# 01_V5_SYS.net
KiCad netlist of a schematic drawn in Altium Designer
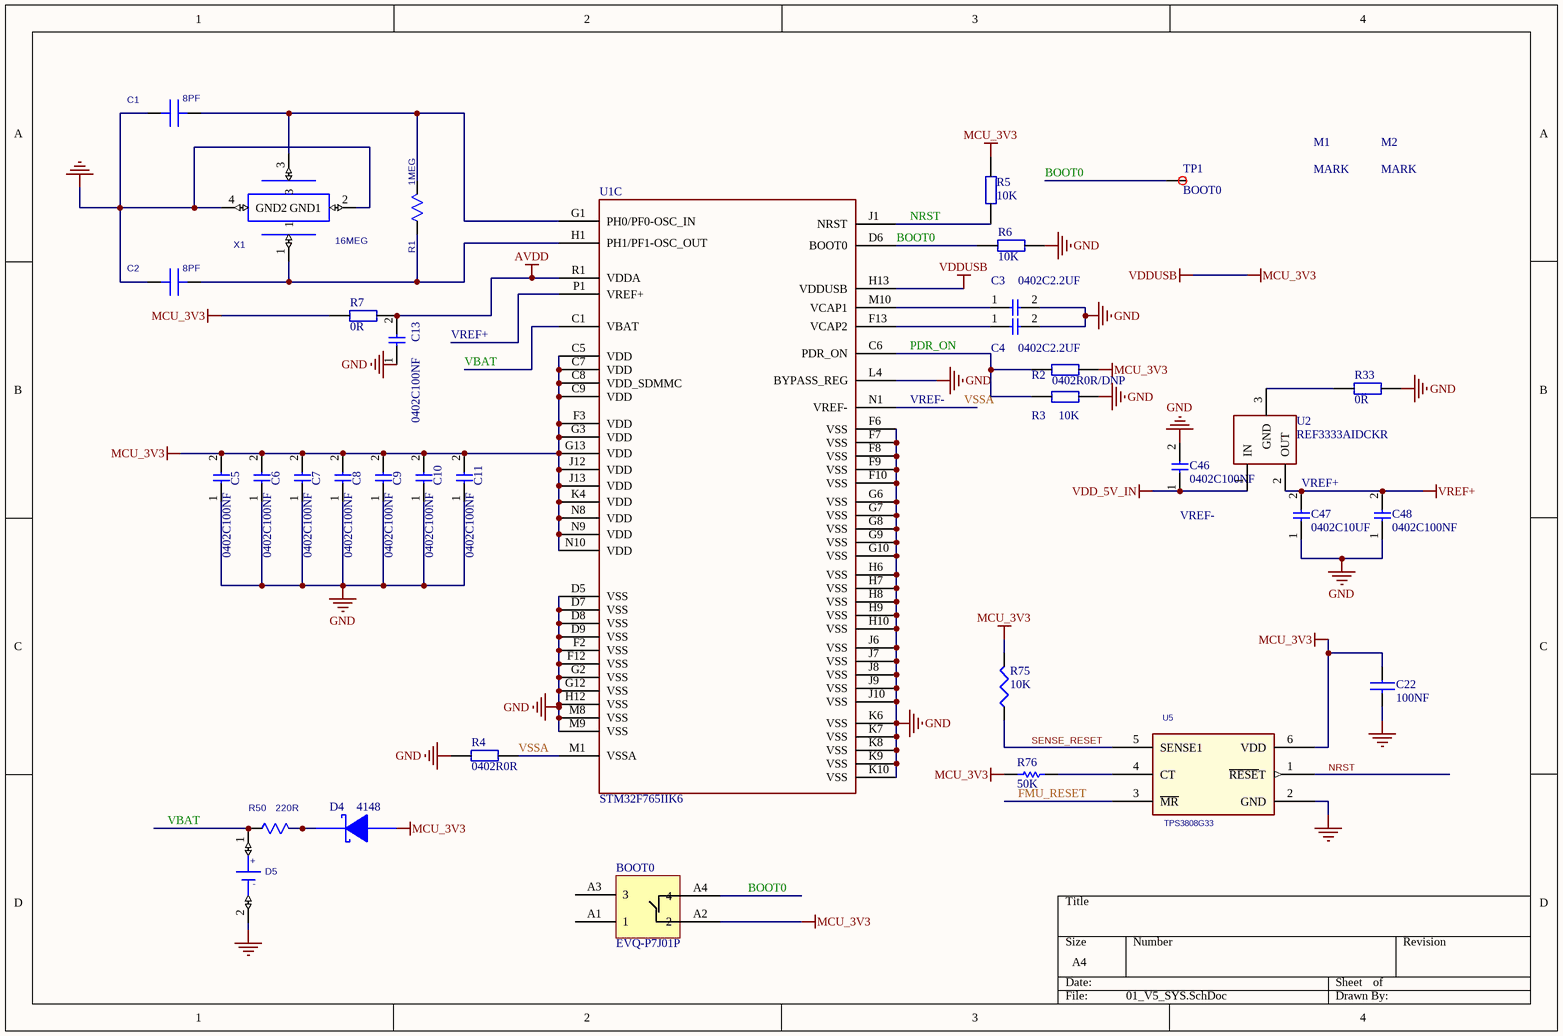
[diagram p0: 01_V5_SYS.SchDoc]

(export (version "E")
  (design (tool "Eeschema 10.0.6"))
  (components
    (comp (ref "BOOT0")
      (value "EVQ-P7J01P")
      (footprint "EVQ-P7J01P")
      (libsource (lib "hack") (part "EVQ-P7J01P"))
    )
    (comp (ref "C1") (value "8PF") (footprint "SC0402") (libsource (lib "*") (part "C")))
    (comp (ref "C2") (value "8PF") (footprint "SC0402") (libsource (lib "*") (part "C")))
    (comp (ref "C3") (value "0402C2.2UF") (footprint "0402C") (libsource (lib "CUAV") (part "0402C2.2UF")))
    (comp (ref "C4") (value "0402C2.2UF") (footprint "0402C") (libsource (lib "CUAV") (part "0402C2.2UF")))
    (comp (ref "C5")
      (value "0402C100NF")
      (footprint "0402C")
      (description "50V 5%")
      (libsource (lib "CUAV") (part "0402C100NF"))
    )
    (comp (ref "C6")
      (value "0402C100NF")
      (footprint "0402C")
      (description "50V 5%")
      (libsource (lib "CUAV") (part "0402C100NF"))
    )
    (comp (ref "C7")
      (value "0402C100NF")
      (footprint "0402C")
      (description "50V 5%")
      (libsource (lib "CUAV") (part "0402C100NF"))
    )
    (comp (ref "C8")
      (value "0402C100NF")
      (footprint "0402C")
      (description "50V 5%")
      (libsource (lib "CUAV") (part "0402C100NF"))
    )
    (comp (ref "C9")
      (value "0402C100NF")
      (footprint "0402C")
      (description "50V 5%")
      (libsource (lib "CUAV") (part "0402C100NF"))
    )
    (comp (ref "C10")
      (value "0402C100NF")
      (footprint "0402C")
      (description "50V 5%")
      (libsource (lib "CUAV") (part "0402C100NF"))
    )
    (comp (ref "C11")
      (value "0402C100NF")
      (footprint "0402C")
      (description "50V 5%")
      (libsource (lib "CUAV") (part "0402C100NF"))
    )
    (comp (ref "C13")
      (value "0402C100NF")
      (footprint "0402C")
      (description "50V 5%")
      (libsource (lib "CUAV") (part "0402C100NF"))
    )
    (comp (ref "C22")
      (value "100NF")
      (footprint "0402cap")
      (libsource (lib "Integrated_Library_RF_FEB_2012") (part "C1005X5R1H104K"))
    )
    (comp (ref "C46") (value "0402C100NF") (footprint "0402C") (libsource (lib "CUAV") (part "0402C2.2UF")))
    (comp (ref "C47") (value "0402C10UF") (footprint "0402C") (libsource (lib "CUAV") (part "0402C2.2UF")))
    (comp (ref "C48") (value "0402C100NF") (footprint "0402C") (libsource (lib "CUAV") (part "0402C2.2UF")))
    (comp (ref "D4")
      (value "4148")
      (footprint "SOD323")
      (description "STPS20M100SG-TR")
      (libsource (lib "TI WEBENCH") (part "D1"))
    )
    (comp (ref "D5")
      (value "PAS414HR-VE5R")
      (footprint "PAS414R-S-VE5R")
      (libsource (lib "*") (part "PWR1-2_1"))
    )
    (comp (ref "M1") (value "MARK") (footprint "MARK") (libsource (lib "CUAV") (part "MARK")))
    (comp (ref "M2") (value "MARK") (footprint "MARK") (libsource (lib "CUAV") (part "MARK")))
    (comp (ref "R1") (value "1MEG") (footprint "SR0402") (libsource (lib "*") (part "R")))
    (comp (ref "R2")
      (value "0402R0R/DNP")
      (footprint "0402R")
      (description "0402R0R 1%")
      (libsource (lib "") (part "0402R0R_2"))
    )
    (comp (ref "R3")
      (value "10K")
      (footprint "0402R")
      (description "0402R0R 1%")
      (libsource (lib "") (part "0402R0R_2"))
    )
    (comp (ref "R4")
      (value "0402R0R")
      (footprint "0402R")
      (description "0402R0R 1%")
      (libsource (lib "") (part "0402R0R_2"))
    )
    (comp (ref "R5")
      (value "10K")
      (footprint "0402R")
      (description "0402R0R 1%")
      (libsource (lib "") (part "0402R0R_1"))
    )
    (comp (ref "R6")
      (value "10K")
      (footprint "0402R")
      (description "0402R0R 1%")
      (libsource (lib "CUAV") (part "0402R0R"))
    )
    (comp (ref "R7")
      (value "0R")
      (footprint "0402R")
      (description "0402R0R 1%")
      (libsource (lib "CUAV") (part "0402R0R"))
    )
    (comp (ref "R33")
      (value "0R")
      (footprint "0402R")
      (description "0402R0R 1%")
      (libsource (lib "CUAV") (part "0402R0R"))
    )
    (comp (ref "R50") (value "220R") (footprint "0402r") (libsource (lib "*") (part "R")))
    (comp (ref "R75")
      (value "10K")
      (footprint "R0402")
      (libsource (lib "Integrated_Library_RF_FEB_2012") (part "RMCF0402FT4K99"))
    )
    (comp (ref "R76")
      (value "50K")
      (footprint "0402R")
      (description "Semiconductor Resistor")
      (libsource (lib "Miscellaneous Devices") (part "Res Semi"))
    )
    (comp (ref "TP1")
      (value "BOOT0")
      (footprint "TP0.75")
      (description "TP_0.75MM")
      (libsource (lib "CUAV") (part "TP_0.75"))
    )
    (comp (ref "U1")
      (value "STM32F765IIK6")
      (footprint "UFBGA176")
      (libsource (lib "CUAV") (part "STM32F765IIK6"))
    )
    (comp (ref "U2")
      (value "REF3333AIDCKR")
      (footprint "SC70")
      (libsource (lib "CUAV") (part "REF3333AIDCKT"))
    )
    (comp (ref "U5")
      (value "TPS3808G33")
      (footprint "SOT-23-6")
      (description "IC VOLT SUPERVISOR 0.9V SOT23-6")
      (fields (field (name "PART #") "102020-0009R") (field (name "MANUFACTURER") "Texas Instruments"))
      (libsource (lib "Integrated_Library_RF_FEB_2012") (part "TPS3808G09DBVR"))
    )
    (comp (ref "X1") (value "16MEG") (footprint "3225") (libsource (lib "*") (part "X_B")))
  )
  (nets
    (net (code "1") (name "/BOOT0") (class "Default")
      (node (ref "BOOT0") (pin "A4") (pinfunction "4_A4") (pintype "passive"))
      (node (ref "R6") (pin "2") (pintype "passive"))
      (node (ref "TP1") (pin "0") (pintype "passive"))
      (node (ref "U1") (pin "D6") (pinfunction "BOOT0_D6") (pintype "passive"))
    )
    (net (code "2") (name "/FMU_RESET") (class "Default")
      (node (ref "U5") (pin "3") (pinfunction "~{MR}_3") (pintype "passive"))
    )
    (net (code "3") (name "/NRST") (class "Default")
      (node (ref "R5") (pin "1") (pintype "passive"))
      (node (ref "U1") (pin "J1") (pinfunction "NRST_J1") (pintype "passive"))
      (node (ref "U5") (pin "1") (pinfunction "~{RESE}T_1") (pintype "output"))
    )
    (net (code "4") (name "/PDR_ON") (class "Default")
      (node (ref "R2") (pin "1") (pintype "passive"))
      (node (ref "R3") (pin "1") (pintype "passive"))
      (node (ref "U1") (pin "C6") (pinfunction "PDR_ON_C6") (pintype "passive"))
    )
    (net (code "5") (name "/SENSE_RESET") (class "Default")
      (node (ref "R75") (pin "1") (pinfunction "1_1") (pintype "passive"))
      (node (ref "U5") (pin "5") (pinfunction "SENSE1_5") (pintype "passive"))
    )
    (net (code "6") (name "/VBAT") (class "Default")
      (node (ref "D5") (pin "1") (pinfunction "+_1") (pintype "bidirectional"))
      (node (ref "R50") (pin "1") (pinfunction "A_1") (pintype "bidirectional"))
      (node (ref "U1") (pin "C1") (pinfunction "VBAT_C1") (pintype "passive"))
    )
    (net (code "7") (name "/VREF-") (class "Default")
      (node (ref "R4") (pin "2") (pintype "passive"))
      (node (ref "U1") (pin "M1") (pinfunction "VSSA_M1") (pintype "passive"))
      (node (ref "U1") (pin "N1") (pinfunction "VREF-_N1") (pintype "passive"))
    )
    (net (code "8") (name "AVDD") (class "Default")
      (node (ref "C13") (pin "2") (pintype "passive"))
      (node (ref "R7") (pin "1") (pintype "passive"))
      (node (ref "U1") (pin "R1") (pinfunction "VDDA_R1") (pintype "passive"))
    )
    (net (code "9") (name "GND") (class "Default")
      (node (ref "C1") (pin "1") (pinfunction "A_1") (pintype "bidirectional"))
      (node (ref "C10") (pin "1") (pintype "passive"))
      (node (ref "C11") (pin "1") (pintype "passive"))
      (node (ref "C13") (pin "1") (pintype "passive"))
      (node (ref "C2") (pin "1") (pinfunction "A_1") (pintype "bidirectional"))
      (node (ref "C22") (pin "2") (pinfunction "2_2") (pintype "passive"))
      (node (ref "C3") (pin "2") (pintype "passive"))
      (node (ref "C4") (pin "2") (pintype "passive"))
      (node (ref "C46") (pin "2") (pintype "passive"))
      (node (ref "C47") (pin "1") (pintype "passive"))
      (node (ref "C48") (pin "1") (pintype "passive"))
      (node (ref "C5") (pin "1") (pintype "passive"))
      (node (ref "C6") (pin "1") (pintype "passive"))
      (node (ref "C7") (pin "1") (pintype "passive"))
      (node (ref "C8") (pin "1") (pintype "passive"))
      (node (ref "C9") (pin "1") (pintype "passive"))
      (node (ref "D5") (pin "2") (pinfunction "-_2") (pintype "bidirectional"))
      (node (ref "R3") (pin "2") (pintype "passive"))
      (node (ref "R33") (pin "1") (pintype "passive"))
      (node (ref "R4") (pin "1") (pintype "passive"))
      (node (ref "R6") (pin "1") (pintype "passive"))
      (node (ref "U1") (pin "D5") (pinfunction "VSS_D5") (pintype "passive"))
      (node (ref "U1") (pin "D7") (pinfunction "VSS_D7") (pintype "passive"))
      (node (ref "U1") (pin "D8") (pinfunction "VSS_D8") (pintype "passive"))
      (node (ref "U1") (pin "D9") (pinfunction "VSS_D9") (pintype "passive"))
      (node (ref "U1") (pin "F10") (pinfunction "VSS_F10") (pintype "passive"))
      (node (ref "U1") (pin "F12") (pinfunction "VSS_F12") (pintype "passive"))
      (node (ref "U1") (pin "F2") (pinfunction "VSS_F2") (pintype "passive"))
      (node (ref "U1") (pin "F6") (pinfunction "VSS_F6") (pintype "passive"))
      (node (ref "U1") (pin "F7") (pinfunction "VSS_F7") (pintype "passive"))
      (node (ref "U1") (pin "F8") (pinfunction "VSS_F8") (pintype "passive"))
      (node (ref "U1") (pin "F9") (pinfunction "VSS_F9") (pintype "passive"))
      (node (ref "U1") (pin "G10") (pinfunction "VSS_G10") (pintype "passive"))
      (node (ref "U1") (pin "G12") (pinfunction "VSS_G12") (pintype "passive"))
      (node (ref "U1") (pin "G2") (pinfunction "VSS_G2") (pintype "passive"))
      (node (ref "U1") (pin "G6") (pinfunction "VSS_G6") (pintype "passive"))
      (node (ref "U1") (pin "G7") (pinfunction "VSS_G7") (pintype "passive"))
      (node (ref "U1") (pin "G8") (pinfunction "VSS_G8") (pintype "passive"))
      (node (ref "U1") (pin "G9") (pinfunction "VSS_G9") (pintype "passive"))
      (node (ref "U1") (pin "H10") (pinfunction "VSS_H10") (pintype "passive"))
      (node (ref "U1") (pin "H12") (pinfunction "VSS_H12") (pintype "passive"))
      (node (ref "U1") (pin "H6") (pinfunction "VSS_H6") (pintype "passive"))
      (node (ref "U1") (pin "H7") (pinfunction "VSS_H7") (pintype "passive"))
      (node (ref "U1") (pin "H8") (pinfunction "VSS_H8") (pintype "passive"))
      (node (ref "U1") (pin "H9") (pinfunction "VSS_H9") (pintype "passive"))
      (node (ref "U1") (pin "J10") (pinfunction "VSS_J10") (pintype "passive"))
      (node (ref "U1") (pin "J6") (pinfunction "VSS_J6") (pintype "passive"))
      (node (ref "U1") (pin "J7") (pinfunction "VSS_J7") (pintype "passive"))
      (node (ref "U1") (pin "J8") (pinfunction "VSS_J8") (pintype "passive"))
      (node (ref "U1") (pin "J9") (pinfunction "VSS_J9") (pintype "passive"))
      (node (ref "U1") (pin "K10") (pinfunction "VSS_K10") (pintype "passive"))
      (node (ref "U1") (pin "K6") (pinfunction "VSS_K6") (pintype "passive"))
      (node (ref "U1") (pin "K7") (pinfunction "VSS_K7") (pintype "passive"))
      (node (ref "U1") (pin "K8") (pinfunction "VSS_K8") (pintype "passive"))
      (node (ref "U1") (pin "K9") (pinfunction "VSS_K9") (pintype "passive"))
      (node (ref "U1") (pin "L4") (pinfunction "BYPASS_REG_L4") (pintype "passive"))
      (node (ref "U1") (pin "M8") (pinfunction "VSS_M8") (pintype "passive"))
      (node (ref "U1") (pin "M9") (pinfunction "VSS_M9") (pintype "passive"))
      (node (ref "U5") (pin "2") (pinfunction "GND_2") (pintype "passive"))
      (node (ref "X1") (pin "2") (pinfunction "GND1_2") (pintype "bidirectional"))
      (node (ref "X1") (pin "4") (pinfunction "GND2_4") (pintype "bidirectional"))
    )
    (net (code "10") (name "MCU_3V3") (class "Default")
      (node (ref "BOOT0") (pin "A2") (pinfunction "2_A2") (pintype "passive"))
      (node (ref "C10") (pin "2") (pintype "passive"))
      (node (ref "C11") (pin "2") (pintype "passive"))
      (node (ref "C22") (pin "1") (pinfunction "1_1") (pintype "passive"))
      (node (ref "C5") (pin "2") (pintype "passive"))
      (node (ref "C6") (pin "2") (pintype "passive"))
      (node (ref "C7") (pin "2") (pintype "passive"))
      (node (ref "C8") (pin "2") (pintype "passive"))
      (node (ref "C9") (pin "2") (pintype "passive"))
      (node (ref "D4") (pin "A") (pinfunction "A_A") (pintype "passive"))
      (node (ref "R2") (pin "2") (pintype "passive"))
      (node (ref "R5") (pin "2") (pintype "passive"))
      (node (ref "R7") (pin "2") (pintype "passive"))
      (node (ref "R75") (pin "2") (pinfunction "2_2") (pintype "passive"))
      (node (ref "R76") (pin "2") (pinfunction "2_2") (pintype "passive"))
      (node (ref "U1") (pin "C5") (pinfunction "VDD_C5") (pintype "passive"))
      (node (ref "U1") (pin "C7") (pinfunction "VDD_C7") (pintype "passive"))
      (node (ref "U1") (pin "C8") (pinfunction "VDD_SDMMC_C8") (pintype "passive"))
      (node (ref "U1") (pin "C9") (pinfunction "VDD_C9") (pintype "passive"))
      (node (ref "U1") (pin "F3") (pinfunction "VDD_F3") (pintype "passive"))
      (node (ref "U1") (pin "G13") (pinfunction "VDD_G13") (pintype "passive"))
      (node (ref "U1") (pin "G3") (pinfunction "VDD_G3") (pintype "passive"))
      (node (ref "U1") (pin "H13") (pinfunction "VDDUSB_H13") (pintype "passive"))
      (node (ref "U1") (pin "J12") (pinfunction "VDD_J12") (pintype "passive"))
      (node (ref "U1") (pin "J13") (pinfunction "VDD_J13") (pintype "passive"))
      (node (ref "U1") (pin "K4") (pinfunction "VDD_K4") (pintype "passive"))
      (node (ref "U1") (pin "N10") (pinfunction "VDD_N10") (pintype "passive"))
      (node (ref "U1") (pin "N8") (pinfunction "VDD_N8") (pintype "passive"))
      (node (ref "U1") (pin "N9") (pinfunction "VDD_N9") (pintype "passive"))
      (node (ref "U5") (pin "6") (pinfunction "VDD_6") (pintype "passive"))
    )
    (net (code "11") (name "Net-(C1-B)") (class "Default")
      (node (ref "C1") (pin "2") (pinfunction "B_2") (pintype "bidirectional"))
      (node (ref "R1") (pin "2") (pinfunction "B_2") (pintype "bidirectional"))
      (node (ref "U1") (pin "G1") (pinfunction "PH0/PF0-OSC_IN_G1") (pintype "passive"))
      (node (ref "X1") (pin "3") (pinfunction "3_3") (pintype "bidirectional"))
    )
    (net (code "12") (name "Net-(C2-B)") (class "Default")
      (node (ref "C2") (pin "2") (pinfunction "B_2") (pintype "bidirectional"))
      (node (ref "R1") (pin "1") (pinfunction "A_1") (pintype "bidirectional"))
      (node (ref "U1") (pin "H1") (pinfunction "PH1/PF1-OSC_OUT_H1") (pintype "passive"))
      (node (ref "X1") (pin "1") (pinfunction "1_1") (pintype "bidirectional"))
    )
    (net (code "13") (name "Net-(R50-B)") (class "Default")
      (node (ref "D4") (pin "K") (pinfunction "K_K") (pintype "passive"))
      (node (ref "R50") (pin "2") (pinfunction "B_2") (pintype "bidirectional"))
    )
    (net (code "14") (name "Net-(U1C-VCAP1)") (class "Default")
      (node (ref "C3") (pin "1") (pintype "passive"))
      (node (ref "U1") (pin "M10") (pinfunction "VCAP1_M10") (pintype "passive"))
    )
    (net (code "15") (name "Net-(U1C-VCAP2)") (class "Default")
      (node (ref "C4") (pin "1") (pintype "passive"))
      (node (ref "U1") (pin "F13") (pinfunction "VCAP2_F13") (pintype "passive"))
    )
    (net (code "16") (name "Net-(U2-GND)") (class "Default")
      (node (ref "R33") (pin "2") (pintype "passive"))
      (node (ref "U2") (pin "3") (pinfunction "GND_3") (pintype "passive"))
    )
    (net (code "17") (name "Net-(U5-CT)") (class "Default")
      (node (ref "R76") (pin "1") (pinfunction "1_1") (pintype "passive"))
      (node (ref "U5") (pin "4") (pinfunction "CT_4") (pintype "passive"))
    )
    (net (code "18") (name "VDD_5V_IN") (class "Default")
      (node (ref "C46") (pin "1") (pintype "passive"))
      (node (ref "U2") (pin "1") (pinfunction "IN_1") (pintype "passive"))
    )
    (net (code "19") (name "VREF+") (class "Default")
      (node (ref "C47") (pin "2") (pintype "passive"))
      (node (ref "C48") (pin "2") (pintype "passive"))
      (node (ref "U1") (pin "P1") (pinfunction "VREF+_P1") (pintype "passive"))
      (node (ref "U2") (pin "2") (pinfunction "OUT_2") (pintype "passive"))
    )
    (net (code "20") (name "unconnected-(BOOT0-1-PadA1)") (class "Default")
      (node (ref "BOOT0") (pin "A1") (pinfunction "1_A1") (pintype "passive"))
    )
    (net (code "21") (name "unconnected-(BOOT0-3-PadA3)") (class "Default")
      (node (ref "BOOT0") (pin "A3") (pinfunction "3_A3") (pintype "passive"))
    )
  )
)
